# 7V_Buck.net
KiCad netlist of a schematic drawn in Altium Designer
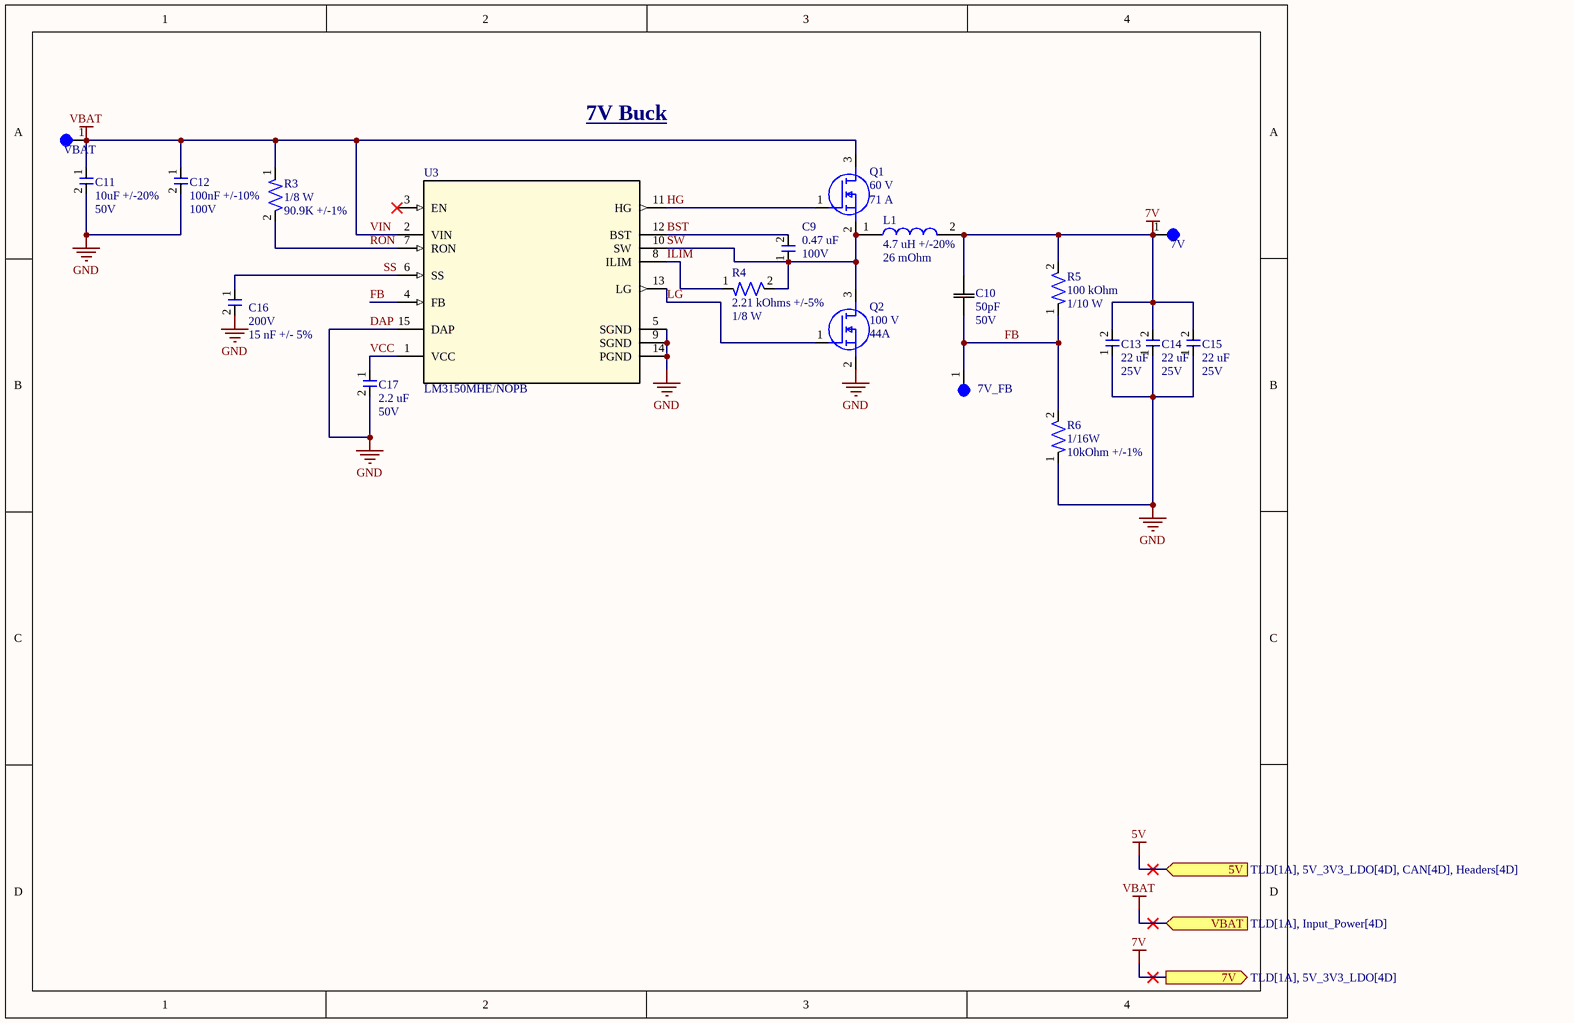
[diagram p0: 7V_Buck.SchDoc]

(export (version "E")
  (design (tool "Eeschema 10.0.6"))
  (components
    (comp (ref "7V")
      (value "5003")
      (footprint "TEST-POINT-0001")
      (description "Oranange PC Test Point, Miniature Phoisphor Bronze Silver Plating Through Hole Mounting Type")
      (libsource (lib "JLC_25") (part "TEST-POINT-0001"))
    )
    (comp (ref "7V_FB")
      (value "5003")
      (footprint "TEST-POINT-0001")
      (description "Oranange PC Test Point, Miniature Phoisphor Bronze Silver Plating Through Hole Mounting Type")
      (libsource (lib "JLC_25") (part "TEST-POINT-0001"))
    )
    (comp (ref "C9")
      (value "KAM21KR72A474KL")
      (footprint "CAP-0805")
      (description "0.47 µF ±10% 100V Ceramic Capacitor X7R 0805 (2012 Metric)")
      (fields
        (field (name "TOLERANCE") "+/- 10%")
        (field (name "CAPACITANCE") "0.47 uF")
        (field (name "VOLTAGE") "100V")
      )
      (libsource (lib "MasterLib") (part "CAP-0.47U-0001"))
    )
    (comp (ref "C10")
      (value "CC0402JRNPO9BN500")
      (footprint "CAP_CC0402_YAG")
      (description "50 pF ±5% 50V Ceramic Capacitor C0G, NP0 0402 (1005 Metric)")
      (fields
        (field (name "CAPACITANCE") "50pF")
        (field (name "VOLTAGE") "50V")
        (field (name "COPYRIGHT") "Copyright (C) 2025 Ultra Librarian. All rights reserved.")
      )
      (libsource (lib "MasterLib") (part "CAP-50p"))
    )
    (comp (ref "C11")
      (value "CL31B106KBHNNNE")
      (footprint "CAP-1206")
      (description "10 µF ±10% 50V Ceramic Capacitor X7R 1206 (3216 Metric)")
      (fields
        (field (name "MANUFACTURER") "Samsung Electro-Mechanics")
        (field (name "CAPACITANCE") "10uF +/-20%")
        (field (name "VOLTAGE RATING") "50V")
      )
      (libsource (lib "MasterLib") (part "CAP-10U-0001"))
    )
    (comp (ref "C12")
      (value "CC0603KRX7R0BB104")
      (footprint "CAP-0603")
      (description "CAP CER 0.1UF 100V X7R 0603")
      (fields
        (field (name "MANUFACTURER") "YAGEO")
        (field (name "CAPACITANCE") "100nF +/-10%")
        (field (name "VOLTAGE RATING") "100V")
      )
      (libsource (lib "MasterLib") (part "CAP-100N-0001"))
    )
    (comp (ref "C13")
      (value "CL32B226KAJNNNE")
      (footprint "CAP-1210")
      (description "22 µF ±10% 25V Ceramic Capacitor X7R 1210 (3225 Metric)")
      (fields
        (field (name "TOLERANCE") "+/- 10%")
        (field (name "CAPACITANCE") "22 uF")
        (field (name "VOLTAGE") "25V")
      )
      (libsource (lib "MasterLib") (part "CAP-22U-0003"))
    )
    (comp (ref "C14")
      (value "CL32B226KAJNNNE")
      (footprint "CAP-1210")
      (description "22 µF ±10% 25V Ceramic Capacitor X7R 1210 (3225 Metric)")
      (fields
        (field (name "TOLERANCE") "+/- 10%")
        (field (name "CAPACITANCE") "22 uF")
        (field (name "VOLTAGE") "25V")
      )
      (libsource (lib "MasterLib") (part "CAP-22U-0003"))
    )
    (comp (ref "C15")
      (value "CL32B226KAJNNNE")
      (footprint "CAP-1210")
      (description "22 µF ±10% 25V Ceramic Capacitor X7R 1210 (3225 Metric)")
      (fields
        (field (name "TOLERANCE") "+/- 10%")
        (field (name "CAPACITANCE") "22 uF")
        (field (name "VOLTAGE") "25V")
      )
      (libsource (lib "MasterLib") (part "CAP-22U-0003"))
    )
    (comp (ref "C16")
      (value "GMC31CG153J200NT")
      (footprint "CAP-1206")
      (description "0.015 µF ±5% 200V Ceramic Capacitor C0G, NP0 1206 (3216 Metric)")
      (fields (field (name "PARAMETER 2") "200V") (field (name "PARAMETER 1") "15 nF +/- 5%"))
      (libsource (lib "MasterLib") (part "CAP-15N-0001"))
    )
    (comp (ref "C17")
      (value "UMK107BBJ225KA-T")
      (footprint "CAP-0603")
      (description "2.2 µF ±10% 50V Ceramic Capacitor X5R 0603 (1608 Metric)")
      (fields (field (name "CAPACITANCE") "2.2 uF") (field (name "OLTAGE") "50V"))
      (libsource (lib "MasterLib") (part "CAP-2.2U-0001"))
    )
    (comp (ref "L1")
      (value "SRN6045TA-4R7M")
      (footprint "PWRIND-4.7U-0001")
      (description "4.7 µH Semi-Shielded Drum Core, Wirewound Inductor 4.5 A 26mOhm Nonstandard")
      (fields (field (name "INDUCTANCE") "4.7 uH +/-20%") (field (name "DCR") "26 mOhm"))
      (libsource (lib "MasterLib") (part "PWRIND-4.7U-0001"))
    )
    (comp (ref "Q1")
      (value "NTMFS5C670NLT1G")
      (footprint "NTMFS5C670NLT1G_ONS")
      (description "N-Channel 60 V 17A (Ta), 71A (Tc) 3.6W (Ta), 61W (Tc) Surface Mount 5-DFN (5x6) (8-SOFL)")
      (fields
        (field (name "MAX VOLTAGE") "60 V")
        (field (name "MAX CURRENT") "71 A")
        (field (name "COPYRIGHT") "Copyright (C) 2025 Ultra Librarian. All rights reserved.")
      )
      (libsource (lib "MasterLib") (part "NMOS-71A-0001"))
    )
    (comp (ref "Q2")
      (value "CSD19534Q5A")
      (footprint "TRANS_CSD19534Q5A")
      (description "N-Channel 100 V 44A (Tc) 3.2W (Ta), 63W (Tc) Surface Mount 8-VSONP (5x6)")
      (fields
        (field (name "MF") "Texas Instruments")
        (field (name "VOLTAGE MAX") "100 V")
        (field (name "CURRENT MAX") "44A")
      )
      (libsource (lib "MasterLib") (part "NMOS-44A-0001"))
    )
    (comp (ref "R3")
      (value "AC0402FR-7W90K9L")
      (footprint "RES-0402")
      (fields (field (name "PARAMETER 2") "1/8 W") (field (name "PARAMETER 1") "90.9K +/-1%"))
      (libsource (lib "MasterLib") (part "RES-90.9K-0001"))
    )
    (comp (ref "R4")
      (value "RT0805BRD072K21L")
      (footprint "RES-0805")
      (description "2.21 kOhms ±0.1% 0.125W, 1/8W Chip Resistor 0805 (2012 Metric) Thin Film")
      (fields (field (name "RESISTANCE") "2.21 kOhms +/-5%") (field (name "POWER") "1/8 W"))
      (libsource (lib "MasterLib") (part "RES-2.21K-0001"))
    )
    (comp (ref "R5")
      (value "RC0603FR-07100KL")
      (footprint "RES-0603")
      (description "100 kOhms ±1% 0.1W, 1/10W Chip Resistor 0603 (1608 Metric) Moisture Resistant Thick Film")
      (fields
        (field (name "TOLERANCE") "+/- 1%")
        (field (name "RESISTANCE") "100 kOhm")
        (field (name "POWER") "1/10 W")
      )
      (libsource (lib "MasterLib") (part "RES-100K-0003"))
    )
    (comp (ref "R6")
      (value "RC0402FR-0710KL")
      (footprint "RES-0402")
      (description "RES 10K OHM 1% 1/16W 0402")
      (fields
        (field (name "MANUFACTURER") "YAGEO")
        (field (name "POWER RATING") "1/16W")
        (field (name "RESISTANCE") "10kOhm +/-1%")
      )
      (libsource (lib "MasterLib") (part "RES-10K-0001"))
    )
    (comp (ref "U3")
      (value "LM3150MHE/NOPB")
      (footprint "MXA14A")
      (description "6V to 42V Synchronous Step-Down Controller with Adjustable Output Voltage 14-HTSSOP -40 to 125")
      (fields (field (name "COPYRIGHT") "Copyright (C) 2025 Ultra Librarian. All rights reserved."))
      (libsource (lib "MasterLib") (part "IC-BUCK_0011"))
    )
    (comp (ref "VBAT")
      (value "5003")
      (footprint "TEST-POINT-0001")
      (description "Oranange PC Test Point, Miniature Phoisphor Bronze Silver Plating Through Hole Mounting Type")
      (libsource (lib "JLC_25") (part "TEST-POINT-0001"))
    )
  )
  (nets
    (net (code "1") (name "/BST") (class "Default")
      (node (ref "C9") (pin "2") (pinfunction "2_2") (pintype "passive"))
      (node (ref "U3") (pin "12") (pinfunction "BST_12") (pintype "passive"))
    )
    (net (code "2") (name "/FB") (class "Default")
      (node (ref "7V_FB") (pin "1") (pinfunction "0_1") (pintype "passive"))
      (node (ref "C10") (pin "1") (pinfunction "1_1") (pintype "passive"))
      (node (ref "R5") (pin "1") (pinfunction "1_1") (pintype "passive"))
      (node (ref "R6") (pin "2") (pinfunction "2_2") (pintype "passive"))
      (node (ref "U3") (pin "4") (pinfunction "FB_4") (pintype "input"))
    )
    (net (code "3") (name "/HG") (class "Default")
      (node (ref "Q1") (pin "1") (pinfunction "G_1") (pintype "passive"))
      (node (ref "U3") (pin "11") (pinfunction "HG_11") (pintype "output"))
    )
    (net (code "4") (name "/ILIM") (class "Default")
      (node (ref "R4") (pin "1") (pinfunction "1_1") (pintype "passive"))
      (node (ref "U3") (pin "8") (pinfunction "ILIM_8") (pintype "passive"))
    )
    (net (code "5") (name "/LG") (class "Default")
      (node (ref "Q2") (pin "1") (pinfunction "G_1") (pintype "passive"))
      (node (ref "U3") (pin "13") (pinfunction "LG_13") (pintype "output"))
    )
    (net (code "6") (name "/RON") (class "Default")
      (node (ref "R3") (pin "2") (pinfunction "2_2") (pintype "passive"))
      (node (ref "U3") (pin "7") (pinfunction "RON_7") (pintype "input"))
    )
    (net (code "7") (name "/SS") (class "Default")
      (node (ref "C16") (pin "1") (pinfunction "1_1") (pintype "passive"))
      (node (ref "U3") (pin "6") (pinfunction "SS_6") (pintype "input"))
    )
    (net (code "8") (name "/SW") (class "Default")
      (node (ref "C9") (pin "1") (pinfunction "1_1") (pintype "passive"))
      (node (ref "L1") (pin "1") (pinfunction "1_1") (pintype "passive"))
      (node (ref "Q1") (pin "2") (pinfunction "S_2") (pintype "passive"))
      (node (ref "Q2") (pin "3") (pinfunction "D_3") (pintype "passive"))
      (node (ref "R4") (pin "2") (pinfunction "2_2") (pintype "passive"))
      (node (ref "U3") (pin "10") (pinfunction "SW_10") (pintype "power_in"))
    )
    (net (code "9") (name "/VCC") (class "Default")
      (node (ref "C17") (pin "1") (pinfunction "1_1") (pintype "passive"))
      (node (ref "U3") (pin "1") (pinfunction "VCC_1") (pintype "power_in"))
    )
    (net (code "11") (name "7V") (class "Default")
      (node (ref "7V") (pin "1") (pinfunction "0_1") (pintype "passive"))
      (node (ref "C10") (pin "2") (pinfunction "2_2") (pintype "passive"))
      (node (ref "C13") (pin "2") (pinfunction "2_2") (pintype "passive"))
      (node (ref "C14") (pin "2") (pinfunction "2_2") (pintype "passive"))
      (node (ref "C15") (pin "2") (pinfunction "2_2") (pintype "passive"))
      (node (ref "L1") (pin "2") (pinfunction "2_2") (pintype "passive"))
      (node (ref "R5") (pin "2") (pinfunction "2_2") (pintype "passive"))
    )
    (net (code "12") (name "GND") (class "Default")
      (node (ref "C11") (pin "2") (pinfunction "2_2") (pintype "passive"))
      (node (ref "C12") (pin "2") (pinfunction "2_2") (pintype "passive"))
      (node (ref "C13") (pin "1") (pinfunction "1_1") (pintype "passive"))
      (node (ref "C14") (pin "1") (pinfunction "1_1") (pintype "passive"))
      (node (ref "C15") (pin "1") (pinfunction "1_1") (pintype "passive"))
      (node (ref "C16") (pin "2") (pinfunction "2_2") (pintype "passive"))
      (node (ref "C17") (pin "2") (pinfunction "2_2") (pintype "passive"))
      (node (ref "Q2") (pin "2") (pinfunction "S_2") (pintype "passive"))
      (node (ref "R6") (pin "1") (pinfunction "1_1") (pintype "passive"))
      (node (ref "U3") (pin "14") (pinfunction "PGND_14") (pintype "power_in"))
      (node (ref "U3") (pin "15") (pinfunction "DAP_15") (pintype "power_in"))
      (node (ref "U3") (pin "5") (pinfunction "SGND_5") (pintype "power_in"))
      (node (ref "U3") (pin "9") (pinfunction "SGND_9") (pintype "power_in"))
    )
    (net (code "13") (name "VBAT") (class "Default")
      (node (ref "C11") (pin "1") (pinfunction "1_1") (pintype "passive"))
      (node (ref "C12") (pin "1") (pinfunction "1_1") (pintype "passive"))
      (node (ref "Q1") (pin "3") (pinfunction "D_3") (pintype "passive"))
      (node (ref "R3") (pin "1") (pinfunction "1_1") (pintype "passive"))
      (node (ref "U3") (pin "2") (pinfunction "VIN_2") (pintype "power_in"))
      (node (ref "VBAT") (pin "1") (pinfunction "0_1") (pintype "passive"))
    )
    (net (code "14") (name "unconnected-(U3-EN-Pad3)") (class "Default")
      (node (ref "U3") (pin "3") (pinfunction "EN_3") (pintype "input+no_connect"))
    )
  )
)
